# ADCBreakout.net
KiCad netlist of a schematic drawn in EAGLE
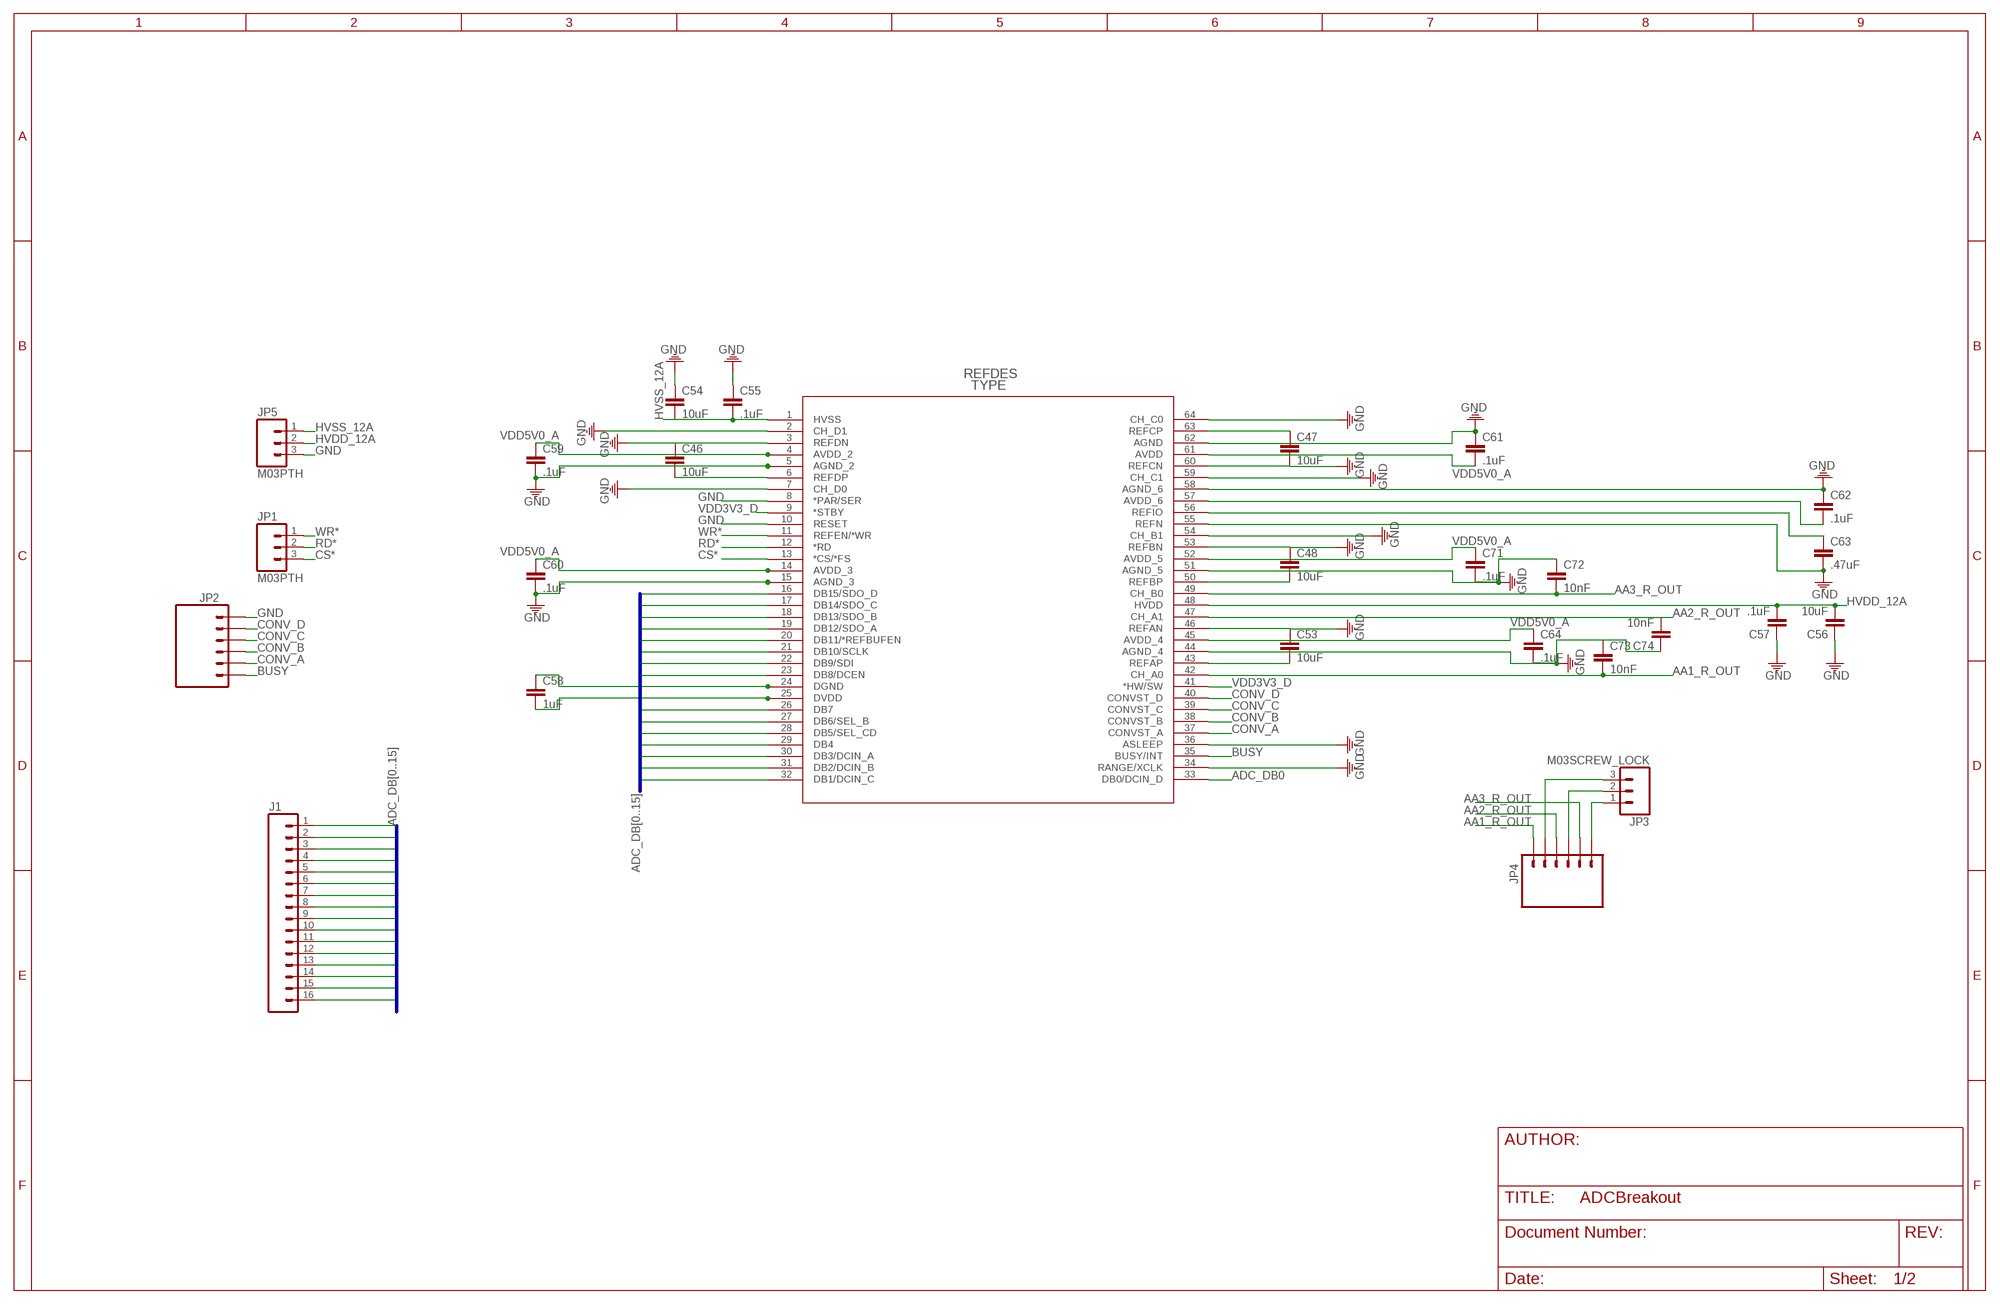
[diagram p0: schematic, sheet 1]
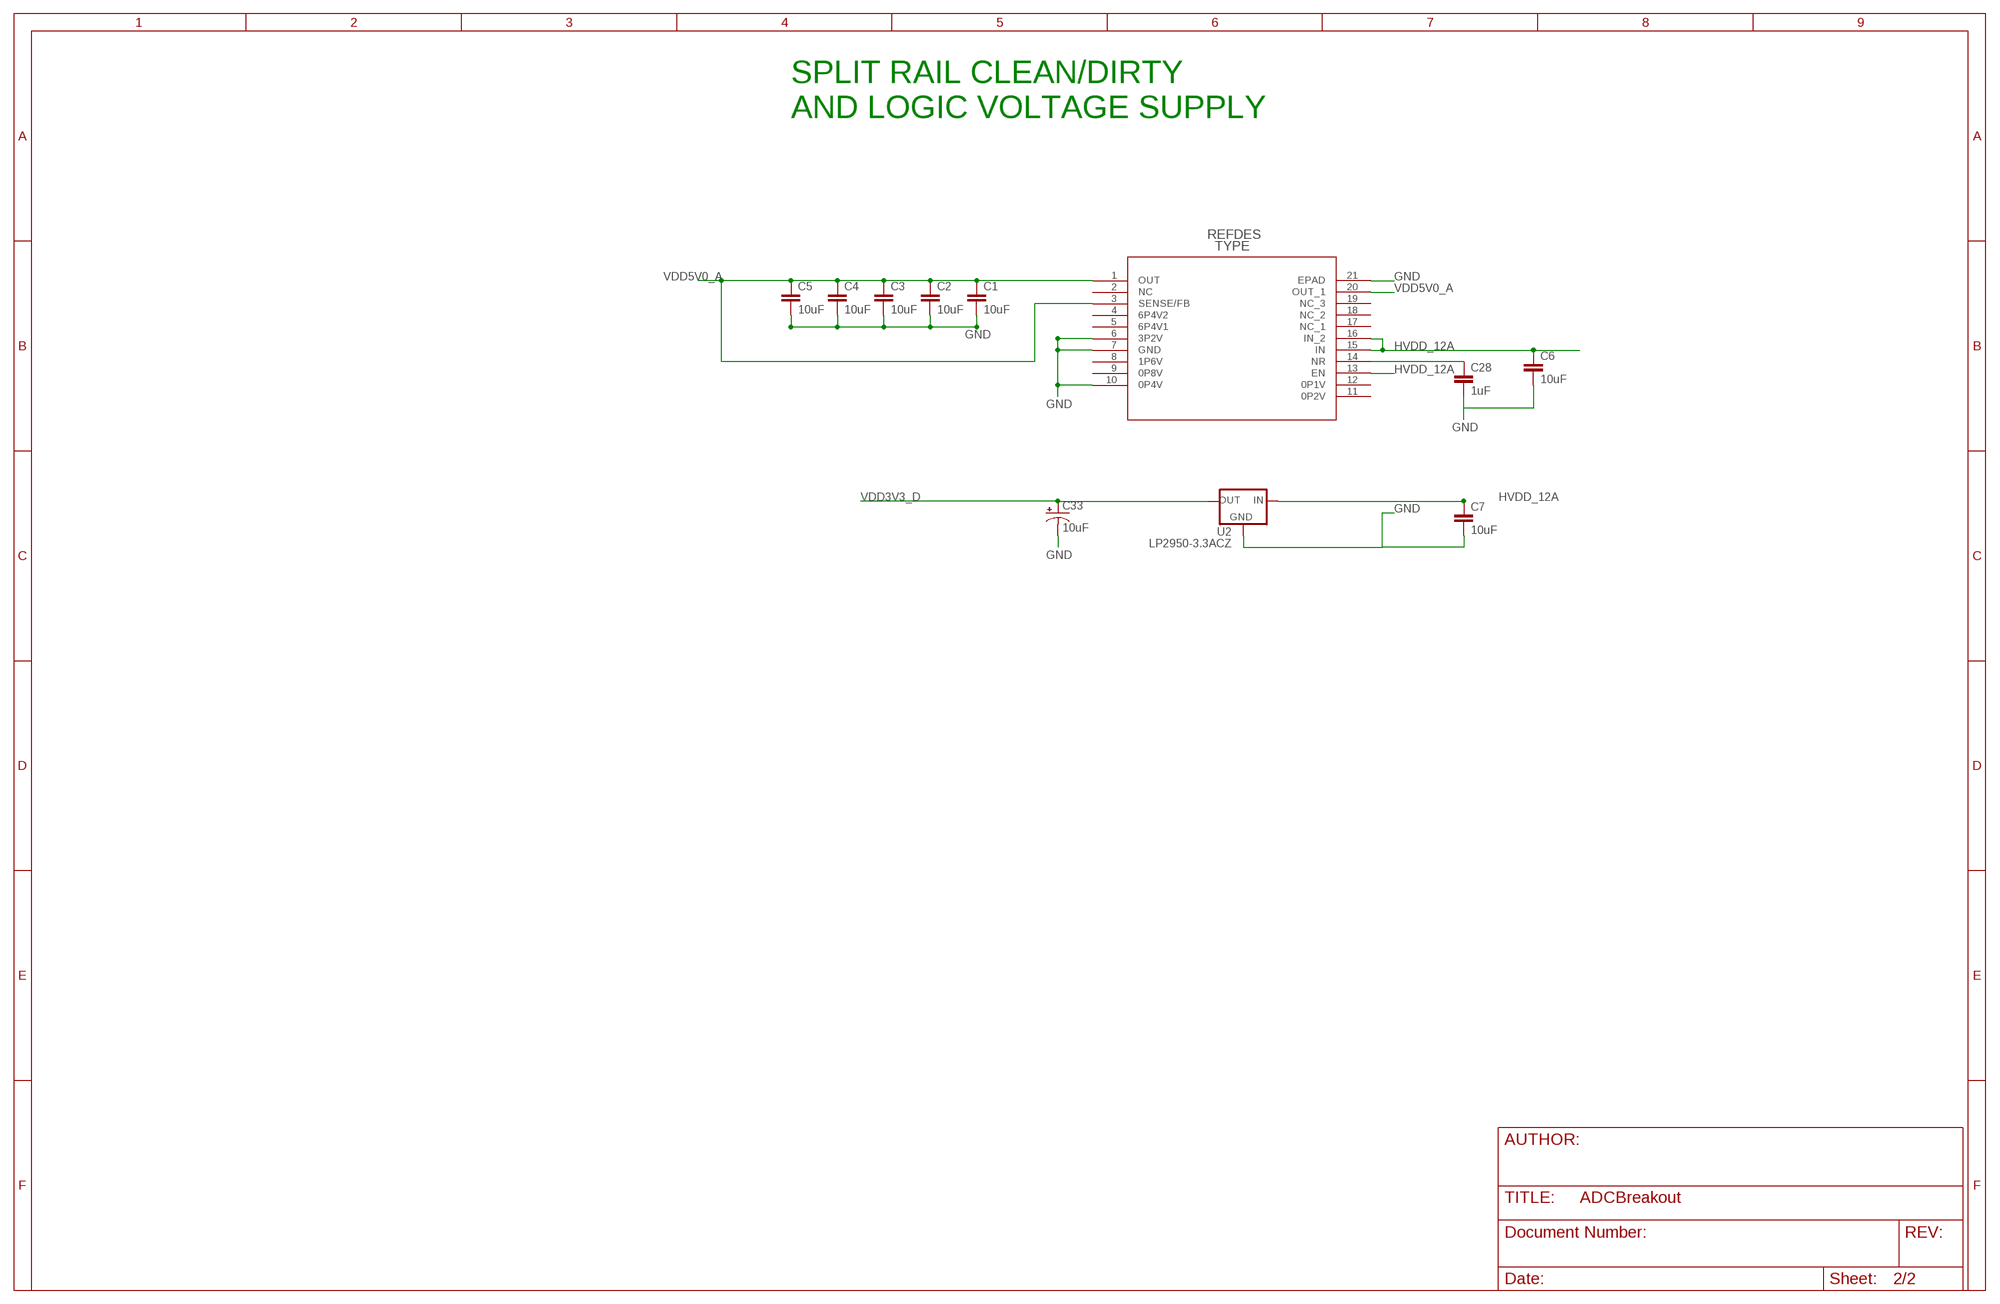
[diagram p1: schematic, sheet 2]

(export (version "E")
  (design (tool "Eeschema 10.0.6"))
  (components
    (comp (ref "C46")
      (value "10uF")
      (footprint "eagle-import:0805")
      (libsource (lib "eagle-import") (part "CAP0805"))
    )
    (comp (ref "C47")
      (value "10uF")
      (footprint "eagle-import:0805")
      (libsource (lib "eagle-import") (part "CAP0805"))
    )
    (comp (ref "C48")
      (value "10uF")
      (footprint "eagle-import:0805")
      (libsource (lib "eagle-import") (part "CAP0805"))
    )
    (comp (ref "C53")
      (value "10uF")
      (footprint "eagle-import:0805")
      (libsource (lib "eagle-import") (part "CAP0805"))
    )
    (comp (ref "C54")
      (value "10uF")
      (footprint "eagle-import:0805")
      (libsource (lib "eagle-import") (part "CAP0805"))
    )
    (comp (ref "C55")
      (value ".1uF")
      (footprint "eagle-import:0805")
      (libsource (lib "eagle-import") (part "CAP0805"))
    )
    (comp (ref "C56")
      (value "10uF")
      (footprint "eagle-import:0805")
      (libsource (lib "eagle-import") (part "CAP0805"))
    )
    (comp (ref "C57")
      (value ".1uF")
      (footprint "eagle-import:0805")
      (libsource (lib "eagle-import") (part "CAP0805"))
    )
    (comp (ref "C58")
      (value "1uF")
      (footprint "eagle-import:0805")
      (libsource (lib "eagle-import") (part "CAP0805"))
    )
    (comp (ref "C59")
      (value ".1uF")
      (footprint "eagle-import:0805")
      (libsource (lib "eagle-import") (part "CAP0805"))
    )
    (comp (ref "C60")
      (value ".1uF")
      (footprint "eagle-import:0805")
      (libsource (lib "eagle-import") (part "CAP0805"))
    )
    (comp (ref "C61")
      (value ".1uF")
      (footprint "eagle-import:0805")
      (libsource (lib "eagle-import") (part "CAP0805"))
    )
    (comp (ref "C62")
      (value ".1uF")
      (footprint "eagle-import:0805")
      (libsource (lib "eagle-import") (part "CAP0805"))
    )
    (comp (ref "C63")
      (value ".47uF")
      (footprint "eagle-import:0805")
      (libsource (lib "eagle-import") (part "CAP0805"))
    )
    (comp (ref "C64")
      (value ".1uF")
      (footprint "eagle-import:0805")
      (libsource (lib "eagle-import") (part "CAP0805"))
    )
    (comp (ref "C71")
      (value ".1uF")
      (footprint "eagle-import:0805")
      (libsource (lib "eagle-import") (part "CAP0805"))
    )
    (comp (ref "C72")
      (value "10nF")
      (footprint "eagle-import:0805")
      (libsource (lib "eagle-import") (part "CAP0805"))
    )
    (comp (ref "C73")
      (value "10nF")
      (footprint "eagle-import:0805")
      (libsource (lib "eagle-import") (part "CAP0805"))
    )
    (comp (ref "C74")
      (value "10nF")
      (footprint "eagle-import:0805")
      (libsource (lib "eagle-import") (part "CAP0805"))
    )
    (comp (ref "J1")
      (value "M16PTH")
      (footprint "eagle-import:1X16")
      (libsource (lib "eagle-import") (part "M16PTH"))
    )
    (comp (ref "JP1")
      (value "M03PTH")
      (footprint "eagle-import:1X03")
      (libsource (lib "eagle-import") (part "M03PTH"))
    )
    (comp (ref "JP2")
      (value "M06SIP")
      (footprint "eagle-import:1X06")
      (libsource (lib "eagle-import") (part "M06SIP"))
    )
    (comp (ref "JP3")
      (value "M03SCREW_LOCK")
      (footprint "eagle-import:SCREWTERMINAL-3.5MM-3_LOCK.007S")
      (libsource (lib "eagle-import") (part "M03SCREW_LOCK"))
    )
    (comp (ref "JP4")
      (value "M06SIP")
      (footprint "eagle-import:1X06")
      (libsource (lib "eagle-import") (part "M06SIP"))
    )
    (comp (ref "JP5")
      (value "M03PTH")
      (footprint "eagle-import:1X03")
      (libsource (lib "eagle-import") (part "M03PTH"))
    )
    (comp (ref "U1")
      (value "ADS8568_PM_64")
      (footprint "eagle-import:PM64")
      (libsource (lib "eagle-import") (part "ADS8568_PM_64"))
    )
    (comp (ref "C1")
      (value "10uF")
      (footprint "eagle-import:0805")
      (libsource (lib "eagle-import") (part "CAP0805"))
    )
    (comp (ref "C2")
      (value "10uF")
      (footprint "eagle-import:0805")
      (libsource (lib "eagle-import") (part "CAP0805"))
    )
    (comp (ref "C3")
      (value "10uF")
      (footprint "eagle-import:0805")
      (libsource (lib "eagle-import") (part "CAP0805"))
    )
    (comp (ref "C4")
      (value "10uF")
      (footprint "eagle-import:0805")
      (libsource (lib "eagle-import") (part "CAP0805"))
    )
    (comp (ref "C5")
      (value "10uF")
      (footprint "eagle-import:0805")
      (libsource (lib "eagle-import") (part "CAP0805"))
    )
    (comp (ref "C6")
      (value "10uF")
      (footprint "eagle-import:0805")
      (libsource (lib "eagle-import") (part "CAP0805"))
    )
    (comp (ref "C7")
      (value "10uF")
      (footprint "eagle-import:0805")
      (libsource (lib "eagle-import") (part "CAP0805"))
    )
    (comp (ref "C28")
      (value "1uF")
      (footprint "eagle-import:0805")
      (libsource (lib "eagle-import") (part "CAP0805"))
    )
    (comp (ref "C33")
      (value "10uF")
      (footprint "eagle-import:CPOL-RADIAL-10UF-25V")
      (libsource (lib "eagle-import") (part "CAP_POLPTH2"))
    )
    (comp (ref "U$3")
      (value "TPS7A4700_RGW_20")
      (footprint "eagle-import:RGW20_3P15X3P15")
      (libsource (lib "eagle-import") (part "TPS7A4700_RGW_20"))
    )
    (comp (ref "U2")
      (value "LP2950-3.3ACZ")
      (footprint "eagle-import:TO92")
      (libsource (lib "eagle-import") (part "LP2950ACZ-3.3"))
    )
  )
  (nets
    (net (code "2") (name "AA1_R_OUT") (class "Default")
      (node (ref "C73") (pin "2") (pinfunction "2_2") (pintype "passive"))
      (node (ref "JP4") (pin "1") (pinfunction "1_1") (pintype "passive"))
      (node (ref "U1") (pin "42") (pinfunction "CH_A0_42") (pintype "passive"))
    )
    (net (code "3") (name "AA2_R_OUT") (class "Default")
      (node (ref "C74") (pin "2") (pinfunction "2_2") (pintype "passive"))
      (node (ref "JP4") (pin "3") (pinfunction "3_3") (pintype "passive"))
      (node (ref "U1") (pin "47") (pinfunction "CH_A1_47") (pintype "passive"))
    )
    (net (code "4") (name "AA3_R_OUT") (class "Default")
      (node (ref "C72") (pin "2") (pinfunction "2_2") (pintype "passive"))
      (node (ref "JP4") (pin "5") (pinfunction "5_5") (pintype "passive"))
      (node (ref "U1") (pin "49") (pinfunction "CH_B0_49") (pintype "passive"))
    )
    (net (code "5") (name "ADC_DB0") (class "Default")
      (node (ref "J1") (pin "1") (pinfunction "1_1") (pintype "passive"))
      (node (ref "U1") (pin "33") (pinfunction "DB0/DCIN_D_33") (pintype "passive"))
    )
    (net (code "6") (name "ADC_DB1") (class "Default")
      (node (ref "J1") (pin "2") (pinfunction "2_2") (pintype "passive"))
      (node (ref "U1") (pin "32") (pinfunction "DB1/DCIN_C_32") (pintype "passive"))
    )
    (net (code "7") (name "ADC_DB2") (class "Default")
      (node (ref "J1") (pin "3") (pinfunction "3_3") (pintype "passive"))
      (node (ref "U1") (pin "31") (pinfunction "DB2/DCIN_B_31") (pintype "passive"))
    )
    (net (code "8") (name "ADC_DB3") (class "Default")
      (node (ref "J1") (pin "4") (pinfunction "4_4") (pintype "passive"))
      (node (ref "U1") (pin "30") (pinfunction "DB3/DCIN_A_30") (pintype "passive"))
    )
    (net (code "9") (name "ADC_DB4") (class "Default")
      (node (ref "J1") (pin "5") (pinfunction "5_5") (pintype "passive"))
      (node (ref "U1") (pin "29") (pinfunction "DB4_29") (pintype "passive"))
    )
    (net (code "10") (name "ADC_DB5") (class "Default")
      (node (ref "J1") (pin "6") (pinfunction "6_6") (pintype "passive"))
      (node (ref "U1") (pin "28") (pinfunction "DB5/SEL_CD_28") (pintype "passive"))
    )
    (net (code "11") (name "ADC_DB6") (class "Default")
      (node (ref "J1") (pin "7") (pinfunction "7_7") (pintype "passive"))
      (node (ref "U1") (pin "27") (pinfunction "DB6/SEL_B_27") (pintype "passive"))
    )
    (net (code "12") (name "ADC_DB7") (class "Default")
      (node (ref "J1") (pin "8") (pinfunction "8_8") (pintype "passive"))
      (node (ref "U1") (pin "26") (pinfunction "DB7_26") (pintype "passive"))
    )
    (net (code "13") (name "ADC_DB8") (class "Default")
      (node (ref "J1") (pin "9") (pinfunction "9_9") (pintype "passive"))
      (node (ref "U1") (pin "23") (pinfunction "DB8/DCEN_23") (pintype "passive"))
    )
    (net (code "14") (name "ADC_DB9") (class "Default")
      (node (ref "J1") (pin "10") (pinfunction "10_10") (pintype "passive"))
      (node (ref "U1") (pin "22") (pinfunction "DB9/SDI_22") (pintype "passive"))
    )
    (net (code "15") (name "ADC_DB10") (class "Default")
      (node (ref "J1") (pin "11") (pinfunction "11_11") (pintype "passive"))
      (node (ref "U1") (pin "21") (pinfunction "DB10/SCLK_21") (pintype "passive"))
    )
    (net (code "16") (name "ADC_DB11") (class "Default")
      (node (ref "J1") (pin "12") (pinfunction "12_12") (pintype "passive"))
      (node (ref "U1") (pin "20") (pinfunction "DB11/*REFBUFEN_20") (pintype "passive"))
    )
    (net (code "17") (name "ADC_DB12") (class "Default")
      (node (ref "J1") (pin "13") (pinfunction "13_13") (pintype "passive"))
      (node (ref "U1") (pin "19") (pinfunction "DB12/SDO_A_19") (pintype "passive"))
    )
    (net (code "18") (name "ADC_DB13") (class "Default")
      (node (ref "J1") (pin "14") (pinfunction "14_14") (pintype "passive"))
      (node (ref "U1") (pin "18") (pinfunction "DB13/SDO_B_18") (pintype "passive"))
    )
    (net (code "19") (name "ADC_DB14") (class "Default")
      (node (ref "J1") (pin "15") (pinfunction "15_15") (pintype "passive"))
      (node (ref "U1") (pin "17") (pinfunction "DB14/SDO_C_17") (pintype "passive"))
    )
    (net (code "20") (name "ADC_DB15") (class "Default")
      (node (ref "J1") (pin "16") (pinfunction "16_16") (pintype "passive"))
      (node (ref "U1") (pin "16") (pinfunction "DB15/SDO_D_16") (pintype "passive"))
    )
    (net (code "21") (name "BUSY") (class "Default")
      (node (ref "JP2") (pin "6") (pinfunction "6_6") (pintype "passive"))
      (node (ref "U1") (pin "35") (pinfunction "BUSY/INT_35") (pintype "passive"))
    )
    (net (code "22") (name "CONV_A") (class "Default")
      (node (ref "JP2") (pin "5") (pinfunction "5_5") (pintype "passive"))
      (node (ref "U1") (pin "37") (pinfunction "CONVST_A_37") (pintype "passive"))
    )
    (net (code "23") (name "CONV_B") (class "Default")
      (node (ref "JP2") (pin "4") (pinfunction "4_4") (pintype "passive"))
      (node (ref "U1") (pin "38") (pinfunction "CONVST_B_38") (pintype "passive"))
    )
    (net (code "24") (name "CONV_C") (class "Default")
      (node (ref "JP2") (pin "3") (pinfunction "3_3") (pintype "passive"))
      (node (ref "U1") (pin "39") (pinfunction "CONVST_C_39") (pintype "passive"))
    )
    (net (code "25") (name "CONV_D") (class "Default")
      (node (ref "JP2") (pin "2") (pinfunction "2_2") (pintype "passive"))
      (node (ref "U1") (pin "40") (pinfunction "CONVST_D_40") (pintype "passive"))
    )
    (net (code "26") (name "CS*") (class "Default")
      (node (ref "JP1") (pin "3") (pinfunction "3_3") (pintype "passive"))
      (node (ref "U1") (pin "13") (pinfunction "*CS/*FS_13") (pintype "passive"))
    )
    (net (code "27") (name "GND") (class "Default")
      (node (ref "C1") (pin "2") (pinfunction "2_2") (pintype "passive"))
      (node (ref "C2") (pin "2") (pinfunction "2_2") (pintype "passive"))
      (node (ref "C28") (pin "2") (pinfunction "2_2") (pintype "passive"))
      (node (ref "C3") (pin "2") (pinfunction "2_2") (pintype "passive"))
      (node (ref "C33") (pin "2") (pinfunction "-_2") (pintype "passive"))
      (node (ref "C4") (pin "2") (pinfunction "2_2") (pintype "passive"))
      (node (ref "C46") (pin "1") (pinfunction "1_1") (pintype "passive"))
      (node (ref "C47") (pin "2") (pinfunction "2_2") (pintype "passive"))
      (node (ref "C48") (pin "1") (pinfunction "1_1") (pintype "passive"))
      (node (ref "C5") (pin "2") (pinfunction "2_2") (pintype "passive"))
      (node (ref "C53") (pin "1") (pinfunction "1_1") (pintype "passive"))
      (node (ref "C54") (pin "1") (pinfunction "1_1") (pintype "passive"))
      (node (ref "C55") (pin "1") (pinfunction "1_1") (pintype "passive"))
      (node (ref "C56") (pin "1") (pinfunction "1_1") (pintype "passive"))
      (node (ref "C57") (pin "1") (pinfunction "1_1") (pintype "passive"))
      (node (ref "C58") (pin "1") (pinfunction "1_1") (pintype "passive"))
      (node (ref "C59") (pin "2") (pinfunction "2_2") (pintype "passive"))
      (node (ref "C6") (pin "2") (pinfunction "2_2") (pintype "passive"))
      (node (ref "C60") (pin "2") (pinfunction "2_2") (pintype "passive"))
      (node (ref "C61") (pin "1") (pinfunction "1_1") (pintype "passive"))
      (node (ref "C62") (pin "1") (pinfunction "1_1") (pintype "passive"))
      (node (ref "C63") (pin "2") (pinfunction "2_2") (pintype "passive"))
      (node (ref "C64") (pin "2") (pinfunction "2_2") (pintype "passive"))
      (node (ref "C7") (pin "2") (pinfunction "2_2") (pintype "passive"))
      (node (ref "C71") (pin "2") (pinfunction "2_2") (pintype "passive"))
      (node (ref "C72") (pin "1") (pinfunction "1_1") (pintype "passive"))
      (node (ref "C73") (pin "1") (pinfunction "1_1") (pintype "passive"))
      (node (ref "C74") (pin "1") (pinfunction "1_1") (pintype "passive"))
      (node (ref "JP2") (pin "1") (pinfunction "1_1") (pintype "passive"))
      (node (ref "JP5") (pin "3") (pinfunction "3_3") (pintype "passive"))
      (node (ref "U$3") (pin "10") (pinfunction "0P4V_10") (pintype "passive"))
      (node (ref "U$3") (pin "21") (pinfunction "EPAD_21") (pintype "passive"))
      (node (ref "U$3") (pin "6") (pinfunction "3P2V_6") (pintype "passive"))
      (node (ref "U$3") (pin "7") (pinfunction "GND_7") (pintype "passive"))
      (node (ref "U1") (pin "10") (pinfunction "RESET_10") (pintype "passive"))
      (node (ref "U1") (pin "15") (pinfunction "AGND_3_15") (pintype "passive"))
      (node (ref "U1") (pin "2") (pinfunction "CH_D1_2") (pintype "passive"))
      (node (ref "U1") (pin "24") (pinfunction "DGND_24") (pintype "passive"))
      (node (ref "U1") (pin "3") (pinfunction "REFDN_3") (pintype "passive"))
      (node (ref "U1") (pin "34") (pinfunction "RANGE/XCLK_34") (pintype "passive"))
      (node (ref "U1") (pin "36") (pinfunction "ASLEEP_36") (pintype "passive"))
      (node (ref "U1") (pin "44") (pinfunction "AGND_4_44") (pintype "passive"))
      (node (ref "U1") (pin "46") (pinfunction "REFAN_46") (pintype "passive"))
      (node (ref "U1") (pin "5") (pinfunction "AGND_2_5") (pintype "passive"))
      (node (ref "U1") (pin "51") (pinfunction "AGND_5_51") (pintype "passive"))
      (node (ref "U1") (pin "53") (pinfunction "REFBN_53") (pintype "passive"))
      (node (ref "U1") (pin "54") (pinfunction "CH_B1_54") (pintype "passive"))
      (node (ref "U1") (pin "55") (pinfunction "REFN_55") (pintype "passive"))
      (node (ref "U1") (pin "58") (pinfunction "AGND_6_58") (pintype "passive"))
      (node (ref "U1") (pin "59") (pinfunction "CH_C1_59") (pintype "passive"))
      (node (ref "U1") (pin "60") (pinfunction "REFCN_60") (pintype "passive"))
      (node (ref "U1") (pin "62") (pinfunction "AGND_62") (pintype "passive"))
      (node (ref "U1") (pin "64") (pinfunction "CH_C0_64") (pintype "passive"))
      (node (ref "U1") (pin "7") (pinfunction "CH_D0_7") (pintype "passive"))
      (node (ref "U1") (pin "8") (pinfunction "*PAR/SER_8") (pintype "passive"))
      (node (ref "U2") (pin "2") (pinfunction "GND_2") (pintype "input"))
    )
    (net (code "28") (name "HVDD_12A") (class "Default")
      (node (ref "C56") (pin "2") (pinfunction "2_2") (pintype "passive"))
      (node (ref "C57") (pin "2") (pinfunction "2_2") (pintype "passive"))
      (node (ref "C6") (pin "1") (pinfunction "1_1") (pintype "passive"))
      (node (ref "C7") (pin "1") (pinfunction "1_1") (pintype "passive"))
      (node (ref "JP5") (pin "2") (pinfunction "2_2") (pintype "passive"))
      (node (ref "U$3") (pin "13") (pinfunction "EN_13") (pintype "passive"))
      (node (ref "U$3") (pin "15") (pinfunction "IN_15") (pintype "passive"))
      (node (ref "U$3") (pin "16") (pinfunction "IN_2_16") (pintype "passive"))
      (node (ref "U1") (pin "48") (pinfunction "HVDD_48") (pintype "passive"))
      (node (ref "U2") (pin "3") (pinfunction "IN_3") (pintype "input"))
    )
    (net (code "29") (name "HVSS_12A") (class "Default")
      (node (ref "C54") (pin "2") (pinfunction "2_2") (pintype "passive"))
      (node (ref "C55") (pin "2") (pinfunction "2_2") (pintype "passive"))
      (node (ref "JP5") (pin "1") (pinfunction "1_1") (pintype "passive"))
      (node (ref "U1") (pin "1") (pinfunction "HVSS_1") (pintype "passive"))
    )
    (net (code "30") (name "Net-(JP3-Pad1)") (class "Default")
      (node (ref "JP3") (pin "1") (pinfunction "1_1") (pintype "passive"))
      (node (ref "JP4") (pin "6") (pinfunction "6_6") (pintype "passive"))
    )
    (net (code "31") (name "Net-(JP3-Pad2)") (class "Default")
      (node (ref "JP3") (pin "2") (pinfunction "2_2") (pintype "passive"))
      (node (ref "JP4") (pin "4") (pinfunction "4_4") (pintype "passive"))
    )
    (net (code "32") (name "Net-(JP3-Pad3)") (class "Default")
      (node (ref "JP3") (pin "3") (pinfunction "3_3") (pintype "passive"))
      (node (ref "JP4") (pin "2") (pinfunction "2_2") (pintype "passive"))
    )
    (net (code "33") (name "Net-(U$3-NR)") (class "Default")
      (node (ref "C28") (pin "1") (pinfunction "1_1") (pintype "passive"))
      (node (ref "U$3") (pin "14") (pinfunction "NR_14") (pintype "passive"))
    )
    (net (code "34") (name "Net-(U1-REFAP)") (class "Default")
      (node (ref "C53") (pin "2") (pinfunction "2_2") (pintype "passive"))
      (node (ref "U1") (pin "43") (pinfunction "REFAP_43") (pintype "passive"))
    )
    (net (code "35") (name "Net-(U1-REFBP)") (class "Default")
      (node (ref "C48") (pin "2") (pinfunction "2_2") (pintype "passive"))
      (node (ref "U1") (pin "50") (pinfunction "REFBP_50") (pintype "passive"))
    )
    (net (code "36") (name "Net-(U1-REFCP)") (class "Default")
      (node (ref "C47") (pin "1") (pinfunction "1_1") (pintype "passive"))
      (node (ref "U1") (pin "63") (pinfunction "REFCP_63") (pintype "passive"))
    )
    (net (code "37") (name "Net-(U1-REFDP)") (class "Default")
      (node (ref "C46") (pin "2") (pinfunction "2_2") (pintype "passive"))
      (node (ref "U1") (pin "6") (pinfunction "REFDP_6") (pintype "passive"))
    )
    (net (code "38") (name "Net-(U1-REFIO)") (class "Default")
      (node (ref "C63") (pin "1") (pinfunction "1_1") (pintype "passive"))
      (node (ref "U1") (pin "56") (pinfunction "REFIO_56") (pintype "passive"))
    )
    (net (code "39") (name "RD*") (class "Default")
      (node (ref "JP1") (pin "2") (pinfunction "2_2") (pintype "passive"))
      (node (ref "U1") (pin "12") (pinfunction "*RD_12") (pintype "passive"))
    )
    (net (code "40") (name "VDD3V3_D") (class "Default")
      (node (ref "C33") (pin "1") (pinfunction "+_1") (pintype "passive"))
      (node (ref "C58") (pin "2") (pinfunction "2_2") (pintype "passive"))
      (node (ref "U1") (pin "25") (pinfunction "DVDD_25") (pintype "passive"))
      (node (ref "U1") (pin "41") (pinfunction "*HW/SW_41") (pintype "passive"))
      (node (ref "U1") (pin "9") (pinfunction "*STBY_9") (pintype "passive"))
      (node (ref "U2") (pin "1") (pinfunction "OUT_1") (pintype "passive"))
    )
    (net (code "41") (name "VDD5V0_A") (class "Default")
      (node (ref "C1") (pin "1") (pinfunction "1_1") (pintype "passive"))
      (node (ref "C2") (pin "1") (pinfunction "1_1") (pintype "passive"))
      (node (ref "C3") (pin "1") (pinfunction "1_1") (pintype "passive"))
      (node (ref "C4") (pin "1") (pinfunction "1_1") (pintype "passive"))
      (node (ref "C5") (pin "1") (pinfunction "1_1") (pintype "passive"))
      (node (ref "C59") (pin "1") (pinfunction "1_1") (pintype "passive"))
      (node (ref "C60") (pin "1") (pinfunction "1_1") (pintype "passive"))
      (node (ref "C61") (pin "2") (pinfunction "2_2") (pintype "passive"))
      (node (ref "C62") (pin "2") (pinfunction "2_2") (pintype "passive"))
      (node (ref "C64") (pin "1") (pinfunction "1_1") (pintype "passive"))
      (node (ref "C71") (pin "1") (pinfunction "1_1") (pintype "passive"))
      (node (ref "U$3") (pin "1") (pinfunction "OUT_1") (pintype "passive"))
      (node (ref "U$3") (pin "20") (pinfunction "OUT_1_20") (pintype "passive"))
      (node (ref "U$3") (pin "3") (pinfunction "SENSE/FB_3") (pintype "passive"))
      (node (ref "U1") (pin "14") (pinfunction "AVDD_3_14") (pintype "passive"))
      (node (ref "U1") (pin "4") (pinfunction "AVDD_2_4") (pintype "passive"))
      (node (ref "U1") (pin "45") (pinfunction "AVDD_4_45") (pintype "passive"))
      (node (ref "U1") (pin "52") (pinfunction "AVDD_5_52") (pintype "passive"))
      (node (ref "U1") (pin "57") (pinfunction "AVDD_6_57") (pintype "passive"))
      (node (ref "U1") (pin "61") (pinfunction "AVDD_61") (pintype "passive"))
    )
    (net (code "42") (name "WR*") (class "Default")
      (node (ref "JP1") (pin "1") (pinfunction "1_1") (pintype "passive"))
      (node (ref "U1") (pin "11") (pinfunction "REFEN/*WR_11") (pintype "passive"))
    )
    (net (code "43") (name "unconnected-(U$3-0P1V-Pad12)") (class "Default")
      (node (ref "U$3") (pin "12") (pinfunction "0P1V_12") (pintype "passive"))
    )
    (net (code "44") (name "unconnected-(U$3-0P2V-Pad11)") (class "Default")
      (node (ref "U$3") (pin "11") (pinfunction "0P2V_11") (pintype "passive"))
    )
    (net (code "45") (name "unconnected-(U$3-0P8V-Pad9)") (class "Default")
      (node (ref "U$3") (pin "9") (pinfunction "0P8V_9") (pintype "passive"))
    )
    (net (code "46") (name "unconnected-(U$3-1P6V-Pad8)") (class "Default")
      (node (ref "U$3") (pin "8") (pinfunction "1P6V_8") (pintype "passive"))
    )
    (net (code "47") (name "unconnected-(U$3-6P4V1-Pad5)") (class "Default")
      (node (ref "U$3") (pin "5") (pinfunction "6P4V1_5") (pintype "passive"))
    )
    (net (code "48") (name "unconnected-(U$3-6P4V2-Pad4)") (class "Default")
      (node (ref "U$3") (pin "4") (pinfunction "6P4V2_4") (pintype "passive"))
    )
    (net (code "49") (name "unconnected-(U$3-NC-Pad2)") (class "Default")
      (node (ref "U$3") (pin "2") (pinfunction "NC_2") (pintype "passive"))
    )
    (net (code "50") (name "unconnected-(U$3-NC_1-Pad17)") (class "Default")
      (node (ref "U$3") (pin "17") (pinfunction "NC_1_17") (pintype "passive"))
    )
    (net (code "51") (name "unconnected-(U$3-NC_2-Pad18)") (class "Default")
      (node (ref "U$3") (pin "18") (pinfunction "NC_2_18") (pintype "passive"))
    )
    (net (code "52") (name "unconnected-(U$3-NC_3-Pad19)") (class "Default")
      (node (ref "U$3") (pin "19") (pinfunction "NC_3_19") (pintype "passive"))
    )
  )
)
